# ePaper_Display.net
KiCad netlist of a schematic drawn in Altium Designer
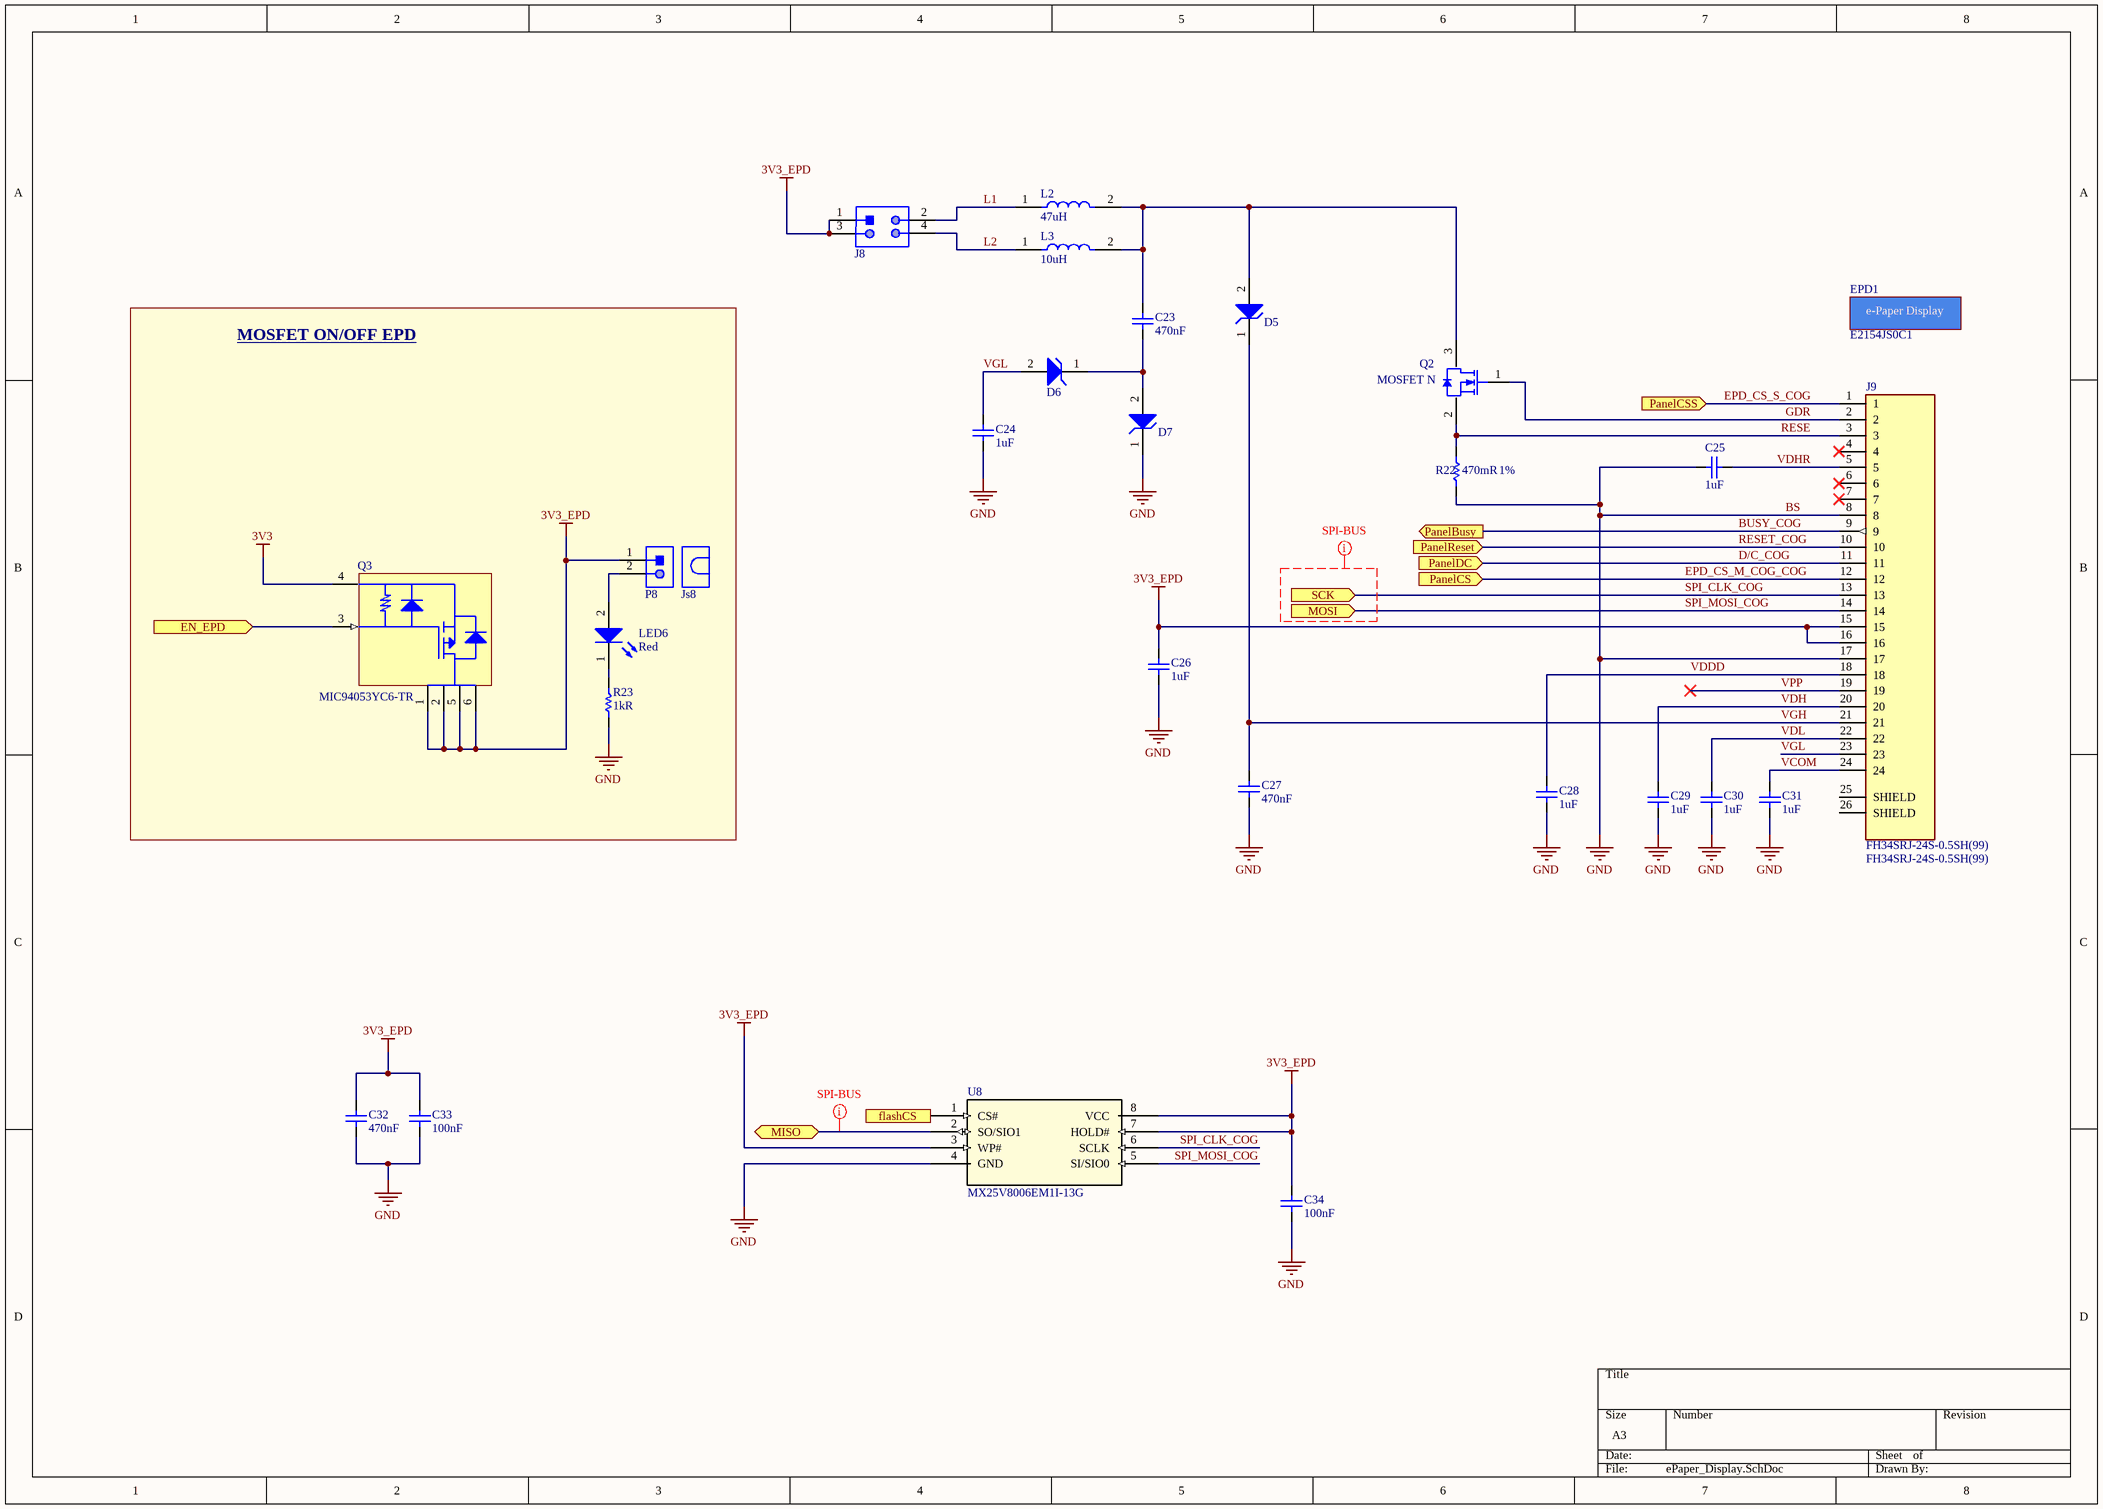
[diagram p0: ePaper_Display.SchDoc]

(export (version "E")
  (design (tool "Eeschema 10.0.6"))
  (components
    (comp (ref "C23")
      (value "470nF")
      (footprint "Cap 0805 (2012 Metric)")
      (description "CAP CER 0.47UF 25V X7R 0805")
      (fields
        (field (name "MANUFACTURER") "Samsung")
        (field (name "MANUFACTURER PART NUMBER") "CL21B474KAFNNNE")
      )
      (libsource (lib "Daniel_Integrated_Library") (part "Capacitor"))
    )
    (comp (ref "C24")
      (value "1uF")
      (footprint "Cap 0805 (2012 Metric)")
      (description "Ceramic capacitor SMD-0805 1000nF /16V X7R# K +-10%, Samsung, RoHS/3000pcs/")
      (fields
        (field (name "MANUFACTURER") "Samsung")
        (field (name "MANUFACTURER PART NUMBER") "CL21B105KOFNNNG")
      )
      (libsource (lib "Daniel_Integrated_Library") (part "Capacitor"))
    )
    (comp (ref "C25")
      (value "1uF")
      (footprint "Cap 0805 (2012 Metric)")
      (description "Ceramic capacitor SMD-0805 1000nF /16V X7R# K +-10%, Samsung, RoHS/3000pcs/")
      (fields
        (field (name "MANUFACTURER") "Samsung")
        (field (name "MANUFACTURER PART NUMBER") "CL21B105KOFNNNG")
      )
      (libsource (lib "Daniel_Integrated_Library") (part "Capacitor"))
    )
    (comp (ref "C26")
      (value "1uF")
      (footprint "Cap 0805 (2012 Metric)")
      (description "Ceramic capacitor SMD-0805 1000nF /16V X7R# K +-10%, Samsung, RoHS/3000pcs/")
      (fields
        (field (name "MANUFACTURER") "Samsung")
        (field (name "MANUFACTURER PART NUMBER") "CL21B105KOFNNNG")
      )
      (libsource (lib "Daniel_Integrated_Library") (part "Capacitor"))
    )
    (comp (ref "C27")
      (value "470nF")
      (footprint "Cap 0805 (2012 Metric)")
      (description "CAP CER 0.47UF 25V X7R 0805")
      (fields
        (field (name "MANUFACTURER") "Samsung")
        (field (name "MANUFACTURER PART NUMBER") "CL21B474KAFNNNE")
      )
      (libsource (lib "Daniel_Integrated_Library") (part "Capacitor"))
    )
    (comp (ref "C28")
      (value "1uF")
      (footprint "Cap 0805 (2012 Metric)")
      (description "Ceramic capacitor SMD-0805 1000nF /16V X7R# K +-10%, Samsung, RoHS/3000pcs/")
      (fields
        (field (name "MANUFACTURER") "Samsung")
        (field (name "MANUFACTURER PART NUMBER") "CL21B105KOFNNNG")
      )
      (libsource (lib "Daniel_Integrated_Library") (part "Capacitor"))
    )
    (comp (ref "C29")
      (value "1uF")
      (footprint "Cap 0805 (2012 Metric)")
      (description "Ceramic capacitor SMD-0805 1000nF /16V X7R# K +-10%, Samsung, RoHS/3000pcs/")
      (fields
        (field (name "MANUFACTURER") "Samsung")
        (field (name "MANUFACTURER PART NUMBER") "CL21B105KOFNNNG")
      )
      (libsource (lib "Daniel_Integrated_Library") (part "Capacitor"))
    )
    (comp (ref "C30")
      (value "1uF")
      (footprint "Cap 0805 (2012 Metric)")
      (description "Ceramic capacitor SMD-0805 1000nF /16V X7R# K +-10%, Samsung, RoHS/3000pcs/")
      (fields
        (field (name "MANUFACTURER") "Samsung")
        (field (name "MANUFACTURER PART NUMBER") "CL21B105KOFNNNG")
      )
      (libsource (lib "Daniel_Integrated_Library") (part "Capacitor"))
    )
    (comp (ref "C31")
      (value "1uF")
      (footprint "Cap 0805 (2012 Metric)")
      (description "Ceramic capacitor SMD-0805 1000nF /16V X7R# K +-10%, Samsung, RoHS/3000pcs/")
      (fields
        (field (name "MANUFACTURER") "Samsung")
        (field (name "MANUFACTURER PART NUMBER") "CL21B105KOFNNNG")
      )
      (libsource (lib "Daniel_Integrated_Library") (part "Capacitor"))
    )
    (comp (ref "C32")
      (value "470nF")
      (footprint "Cap 0805 (2012 Metric)")
      (description "CAP CER 0.47UF 25V X7R 0805")
      (fields
        (field (name "MANUFACTURER") "Samsung")
        (field (name "MANUFACTURER PART NUMBER") "CL21B474KAFNNNE")
      )
      (libsource (lib "Daniel_Integrated_Library") (part "Capacitor"))
    )
    (comp (ref "C33")
      (value "100nF")
      (footprint "Cap 0805 (2012 Metric)")
      (fields
        (field (name "MANUFACTURER") "Yageo")
        (field (name "MANUFACTURER PART NUMBER") "CC0805ZRY5V9BB104")
        (field (name "TOLERANCE") "80%")
      )
      (libsource (lib "Daniel_Integrated_Library") (part "Capacitor"))
    )
    (comp (ref "C34")
      (value "100nF")
      (footprint "Cap 0805 (2012 Metric)")
      (fields
        (field (name "MANUFACTURER") "Yageo")
        (field (name "MANUFACTURER PART NUMBER") "CC0805ZRY5V9BB104")
        (field (name "TOLERANCE") "80%")
      )
      (libsource (lib "Daniel_Integrated_Library") (part "Capacitor"))
    )
    (comp (ref "D5")
      (value "Diode")
      (footprint "Diode SOD123")
      (description "DIODE GEN PURP 75V 150MA 0603")
      (fields
        (field (name "MANUFACTURER") "Taiwan Semiconductor")
        (field (name "MANUFACTURER PART NUMBER") "TS4148CRZG")
      )
      (libsource (lib "Daniel_Integrated_Library") (part "Diode"))
    )
    (comp (ref "D6")
      (value "Diode")
      (footprint "Diode SOD123")
      (description "DIODE GEN PURP 75V 150MA 0603")
      (fields
        (field (name "MANUFACTURER") "Taiwan Semiconductor")
        (field (name "MANUFACTURER PART NUMBER") "TS4148CRZG")
      )
      (libsource (lib "Daniel_Integrated_Library") (part "Diode"))
    )
    (comp (ref "D7")
      (value "Diode")
      (footprint "Diode SOD123")
      (description "DIODE GEN PURP 75V 150MA 0603")
      (fields
        (field (name "MANUFACTURER") "Taiwan Semiconductor")
        (field (name "MANUFACTURER PART NUMBER") "TS4148CRZG")
      )
      (libsource (lib "Daniel_Integrated_Library") (part "Diode"))
    )
    (comp (ref "EPD1")
      (value "E2154JS0C1")
      (description "1.54\" Epd, Spectra, W.itc")
      (fields
        (field (name "MANUFACTURER") "Pervasive Displays")
        (field (name "MANUFACTURER PART NUMBER") "E2154JS0C1")
      )
      (libsource (lib "stratos") (part "ePaper-E2154JS0C1"))
    )
    (comp (ref "J8")
      (value "Header 2x2")
      (footprint "Header 2x2")
      (libsource (lib "Daniel_Integrated_Library") (part "Header 2x2"))
    )
    (comp (ref "J9")
      (value "FH34SRJ-24S-0.5SH(99)")
      (footprint "FH34SRJ-24S-0.5SH(99)")
      (description "CONN FPC/FFC 24POS .5MM")
      (fields
        (field (name "MANUFACTURER") "Hirose")
        (field (name "MANUFACTURER PART NUMBER") "FH34SRJ-24S-0.5SH(99)")
      )
      (libsource (lib "stratos") (part "FH34SRJ-24S-0.5SH(99)"))
    )
    (comp (ref "Js8")
      (value "Jumper (2x1)")
      (footprint "Header JMP 2x1")
      (description "2 (1 x 2) Position Shunt Connector Black Open Top 0.100\" (2.54mm) Gold")
      (fields
        (field (name "MANUFACTURER") "Sullins")
        (field (name "MANUFACTURER PART NUMBER") "QPC02SXGN-RC")
      )
      (libsource (lib "Daniel_Integrated_Library") (part "Jumper (2x1)"))
    )
    (comp (ref "L2")
      (value "47uH")
      (footprint "Ind 0805 (2012 METRIC)")
      (description "Inductor Power Shielded Multi-Layer 47uH 20% 2MHz Ferrite 0.17A 4.81Ohm DCR 0805 T/R")
      (fields
        (field (name "MANUFACTURER") "TDK")
        (field (name "MANUFACTURER PART NUMBER") "MLZ2012M470WT000")
      )
      (libsource (lib "Daniel_Integrated_Library") (part "Inductor"))
    )
    (comp (ref "L3")
      (value "10uH")
      (footprint "Ind 0805 (2012 METRIC)")
      (fields
        (field (name "MANUFACTURER") "TDK")
        (field (name "MANUFACTURER PART NUMBER") "MLZ2012M100WT000")
        (field (name "TOLERANCE") "20%")
      )
      (libsource (lib "Daniel_Integrated_Library") (part "Inductor"))
    )
    (comp (ref "LED6")
      (value "Red")
      (footprint "LED 0805(2012 METRIC)")
      (description "SMD LED red 2.4 V 0805, 150080RS75000, Würth Elektronik")
      (fields
        (field (name "MANUFACTURER") "Wurth Electronics")
        (field (name "MANUFACTURER PART NUMBER") "150080RS75000")
      )
      (libsource (lib "Daniel_Integrated_Library") (part "LED"))
    )
    (comp (ref "P8")
      (value "Header 2x1")
      (footprint "Header 2x1")
      (description "Connector Header Through Hole 2 position 0.100\" (2.54mm)")
      (fields
        (field (name "MANUFACTURER") "Amphenol FCI")
        (field (name "MANUFACTURER PART NUMBER") "68001-402HLF")
      )
      (libsource (lib "Daniel_Integrated_Library") (part "Header 2x1"))
    )
    (comp (ref "Q2")
      (value "MOSFET N")
      (footprint "Mosfet-N")
      (description "Trans MOSFET N-CH 60V 0.115A 3-Pin SOT-23 T/R")
      (fields
        (field (name "MANUFACTURER") "ON Semiconductor")
        (field (name "MANUFACTURER PART NUMBER") "2N7002LT1G")
      )
      (libsource (lib "stratos") (part "MOSFET N"))
    )
    (comp (ref "Q3")
      (value "MIC94053YC6-TR")
      (footprint "SC-70-6")
      (description "P-Channel 6V 2A (Ta) 270mW (Ta) Surface Mount SC-70-6")
      (fields (field (name "MANUFACTURER") "Microchip"))
      (libsource (lib "Daniel_Integrated_Library") (part "TransistorMosfet(Load)"))
    )
    (comp (ref "R22")
      (value "470mR")
      (footprint "Res 0603 (1608 Metric)")
      (description "Res Thick Film 0603 0.47 Ohm 1% 1/10W ±200ppm/°C Molded SMD SMD Paper Tape on Plastic Reel")
      (fields
        (field (name "MANUFACTURER") "Bourns")
        (field (name "MANUFACTURER PART NUMBER") "CRL0603-FW-R470ELF")
        (field (name "TOLERANCE") "1%")
      )
      (libsource (lib "Daniel_Integrated_Library") (part "Resistor"))
    )
    (comp (ref "R23")
      (value "1kR")
      (footprint "Res 0805 (2012 Metric)")
      (description "RES 1K OHM 1% 1/4W 0805")
      (fields
        (field (name "MANUFACTURER") "Stackpole Electronics")
        (field (name "MANUFACTURER PART NUMBER") "RNCP0805FTD1K00")
      )
      (libsource (lib "Daniel_Integrated_Library") (part "Resistor"))
    )
    (comp (ref "U8")
      (value "MX25V8006EM1I-13G")
      (footprint "MX25V8006EM1I-13G")
      (description "MX25U Series 3.6 V 8 Mb (8 M x 1 / 4 M x 2) Surface Mount Serial Flash -SOP - 8")
      (fields
        (field (name "MANUFACTURER") "Macronix")
        (field (name "MANUFACTURER PART NUMBER") "MX25V8006EM1I-13G")
      )
      (libsource (lib "stratos") (part "MX25V8006EM1I-13G"))
    )
  )
  (nets
    (net (code "1") (name "/BUSY_COG") (class "Default")
      (node (ref "J9") (pin "9") (pinfunction "9_9") (pintype "output"))
    )
    (net (code "2") (name "/D{slash}C_COG") (class "Default")
      (node (ref "J9") (pin "11") (pinfunction "11_11") (pintype "passive"))
    )
    (net (code "3") (name "/EN_EPD") (class "Default")
      (node (ref "Q3") (pin "3") (pinfunction "G_3") (pintype "input"))
    )
    (net (code "4") (name "/EPD_CS_M_COG_COG") (class "Default")
      (node (ref "J9") (pin "12") (pinfunction "12_12") (pintype "passive"))
    )
    (net (code "5") (name "/EPD_CS_S_COG") (class "Default")
      (node (ref "J9") (pin "1") (pinfunction "1_1") (pintype "passive"))
    )
    (net (code "6") (name "/GDR") (class "Default")
      (node (ref "J9") (pin "2") (pinfunction "2_2") (pintype "passive"))
      (node (ref "Q2") (pin "1") (pinfunction "G_1") (pintype "passive"))
    )
    (net (code "7") (name "/L1") (class "Default")
      (node (ref "J8") (pin "2") (pinfunction "2_2") (pintype "passive"))
      (node (ref "L2") (pin "1") (pinfunction "1_1") (pintype "passive"))
    )
    (net (code "8") (name "/L2") (class "Default")
      (node (ref "J8") (pin "4") (pinfunction "4_4") (pintype "passive"))
      (node (ref "L3") (pin "1") (pinfunction "1_1") (pintype "passive"))
    )
    (net (code "9") (name "/MISO") (class "Default")
      (node (ref "U8") (pin "2") (pinfunction "SO/SIO1_2") (pintype "bidirectional"))
    )
    (net (code "10") (name "/RESE") (class "Default")
      (node (ref "J9") (pin "3") (pinfunction "3_3") (pintype "passive"))
      (node (ref "Q2") (pin "2") (pinfunction "S_2") (pintype "passive"))
      (node (ref "R22") (pin "1") (pinfunction "1_1") (pintype "passive"))
    )
    (net (code "11") (name "/RESET_COG") (class "Default")
      (node (ref "J9") (pin "10") (pinfunction "10_10") (pintype "passive"))
    )
    (net (code "12") (name "/SPI_CLK_COG") (class "Default")
      (node (ref "J9") (pin "13") (pinfunction "13_13") (pintype "passive"))
      (node (ref "U8") (pin "6") (pinfunction "SCLK_6") (pintype "input"))
    )
    (net (code "13") (name "/SPI_MOSI_COG") (class "Default")
      (node (ref "J9") (pin "14") (pinfunction "14_14") (pintype "passive"))
      (node (ref "U8") (pin "5") (pinfunction "SI/SIO0_5") (pintype "input"))
    )
    (net (code "14") (name "/VCOM") (class "Default")
      (node (ref "C31") (pin "1") (pinfunction "1_1") (pintype "passive"))
      (node (ref "J9") (pin "24") (pinfunction "24_24") (pintype "passive"))
    )
    (net (code "15") (name "/VDDD") (class "Default")
      (node (ref "C28") (pin "1") (pinfunction "1_1") (pintype "passive"))
      (node (ref "J9") (pin "18") (pinfunction "18_18") (pintype "passive"))
    )
    (net (code "16") (name "/VDH") (class "Default")
      (node (ref "C29") (pin "1") (pinfunction "1_1") (pintype "passive"))
      (node (ref "J9") (pin "20") (pinfunction "20_20") (pintype "passive"))
    )
    (net (code "17") (name "/VDHR") (class "Default")
      (node (ref "C25") (pin "1") (pinfunction "1_1") (pintype "passive"))
      (node (ref "J9") (pin "5") (pinfunction "5_5") (pintype "passive"))
    )
    (net (code "18") (name "/VDL") (class "Default")
      (node (ref "C30") (pin "1") (pinfunction "1_1") (pintype "passive"))
      (node (ref "J9") (pin "22") (pinfunction "22_22") (pintype "passive"))
    )
    (net (code "19") (name "/VGH") (class "Default")
      (node (ref "C27") (pin "1") (pinfunction "1_1") (pintype "passive"))
      (node (ref "D5") (pin "1") (pinfunction "K_1") (pintype "passive"))
      (node (ref "J9") (pin "21") (pinfunction "21_21") (pintype "passive"))
    )
    (net (code "20") (name "/VGL") (class "Default")
      (node (ref "C24") (pin "1") (pinfunction "1_1") (pintype "passive"))
      (node (ref "D6") (pin "2") (pinfunction "A_2") (pintype "passive"))
      (node (ref "J9") (pin "23") (pinfunction "23_23") (pintype "passive"))
    )
    (net (code "21") (name "/VPP") (class "Default")
      (node (ref "J9") (pin "19") (pinfunction "19_19") (pintype "passive+no_connect"))
    )
    (net (code "22") (name "/flashCS") (class "Default")
      (node (ref "U8") (pin "1") (pinfunction "CS#_1") (pintype "input"))
    )
    (net (code "23") (name "3V3") (class "Default")
      (node (ref "Q3") (pin "4") (pinfunction "S_4") (pintype "passive"))
    )
    (net (code "24") (name "3V3_EPD") (class "Default")
      (node (ref "C26") (pin "1") (pinfunction "1_1") (pintype "passive"))
      (node (ref "C32") (pin "1") (pinfunction "1_1") (pintype "passive"))
      (node (ref "C33") (pin "1") (pinfunction "1_1") (pintype "passive"))
      (node (ref "C34") (pin "1") (pinfunction "1_1") (pintype "passive"))
      (node (ref "J8") (pin "1") (pinfunction "1_1") (pintype "passive"))
      (node (ref "J8") (pin "3") (pinfunction "3_3") (pintype "passive"))
      (node (ref "J9") (pin "15") (pinfunction "15_15") (pintype "passive"))
      (node (ref "J9") (pin "16") (pinfunction "16_16") (pintype "passive"))
      (node (ref "P8") (pin "1") (pinfunction "1_1") (pintype "passive"))
      (node (ref "Q3") (pin "1") (pinfunction "D_1") (pintype "passive"))
      (node (ref "Q3") (pin "2") (pinfunction "D_2") (pintype "passive"))
      (node (ref "Q3") (pin "5") (pinfunction "D_5") (pintype "passive"))
      (node (ref "Q3") (pin "6") (pinfunction "D_6") (pintype "passive"))
      (node (ref "U8") (pin "3") (pinfunction "WP#_3") (pintype "input"))
      (node (ref "U8") (pin "7") (pinfunction "HOLD#_7") (pintype "input"))
      (node (ref "U8") (pin "8") (pinfunction "VCC_8") (pintype "power_in"))
    )
    (net (code "25") (name "GND") (class "Default")
      (node (ref "C24") (pin "2") (pinfunction "2_2") (pintype "passive"))
      (node (ref "C25") (pin "2") (pinfunction "2_2") (pintype "passive"))
      (node (ref "C26") (pin "2") (pinfunction "2_2") (pintype "passive"))
      (node (ref "C27") (pin "2") (pinfunction "2_2") (pintype "passive"))
      (node (ref "C28") (pin "2") (pinfunction "2_2") (pintype "passive"))
      (node (ref "C29") (pin "2") (pinfunction "2_2") (pintype "passive"))
      (node (ref "C30") (pin "2") (pinfunction "2_2") (pintype "passive"))
      (node (ref "C31") (pin "2") (pinfunction "2_2") (pintype "passive"))
      (node (ref "C32") (pin "2") (pinfunction "2_2") (pintype "passive"))
      (node (ref "C33") (pin "2") (pinfunction "2_2") (pintype "passive"))
      (node (ref "C34") (pin "2") (pinfunction "2_2") (pintype "passive"))
      (node (ref "D7") (pin "1") (pinfunction "K_1") (pintype "passive"))
      (node (ref "J9") (pin "17") (pinfunction "17_17") (pintype "passive"))
      (node (ref "J9") (pin "8") (pinfunction "8_8") (pintype "passive"))
      (node (ref "R22") (pin "2") (pinfunction "2_2") (pintype "passive"))
      (node (ref "R23") (pin "2") (pinfunction "2_2") (pintype "passive"))
      (node (ref "U8") (pin "4") (pinfunction "GND_4") (pintype "passive"))
    )
    (net (code "26") (name "Net-(D5-A)") (class "Default")
      (node (ref "C23") (pin "1") (pinfunction "1_1") (pintype "passive"))
      (node (ref "D5") (pin "2") (pinfunction "A_2") (pintype "passive"))
      (node (ref "L2") (pin "2") (pinfunction "2_2") (pintype "passive"))
      (node (ref "L3") (pin "2") (pinfunction "2_2") (pintype "passive"))
      (node (ref "Q2") (pin "3") (pinfunction "D_3") (pintype "passive"))
    )
    (net (code "27") (name "Net-(D6-K)") (class "Default")
      (node (ref "C23") (pin "2") (pinfunction "2_2") (pintype "passive"))
      (node (ref "D6") (pin "1") (pinfunction "K_1") (pintype "passive"))
      (node (ref "D7") (pin "2") (pinfunction "A_2") (pintype "passive"))
    )
    (net (code "28") (name "Net-(LED6-A)") (class "Default")
      (node (ref "LED6") (pin "2") (pinfunction "A_2") (pintype "passive"))
      (node (ref "P8") (pin "2") (pinfunction "2_2") (pintype "passive"))
    )
    (net (code "29") (name "Net-(LED6-K)") (class "Default")
      (node (ref "LED6") (pin "1") (pinfunction "K_1") (pintype "passive"))
      (node (ref "R23") (pin "1") (pinfunction "1_1") (pintype "passive"))
    )
    (net (code "30") (name "unconnected-(J9-Pad4)") (class "Default")
      (node (ref "J9") (pin "4") (pinfunction "4_4") (pintype "passive+no_connect"))
    )
    (net (code "31") (name "unconnected-(J9-Pad6)") (class "Default")
      (node (ref "J9") (pin "6") (pinfunction "6_6") (pintype "passive+no_connect"))
    )
    (net (code "32") (name "unconnected-(J9-Pad7)") (class "Default")
      (node (ref "J9") (pin "7") (pinfunction "7_7") (pintype "passive+no_connect"))
    )
    (net (code "33") (name "unconnected-(J9-SHIELD-Pad25)") (class "Default")
      (node (ref "J9") (pin "25") (pinfunction "SHIELD_25") (pintype "passive"))
    )
    (net (code "34") (name "unconnected-(J9-SHIELD-Pad26)") (class "Default")
      (node (ref "J9") (pin "26") (pinfunction "SHIELD_26") (pintype "passive"))
    )
  )
)
